# arduino_uno_with__motor_driver.net
KiCad netlist of a schematic drawn in EAGLE
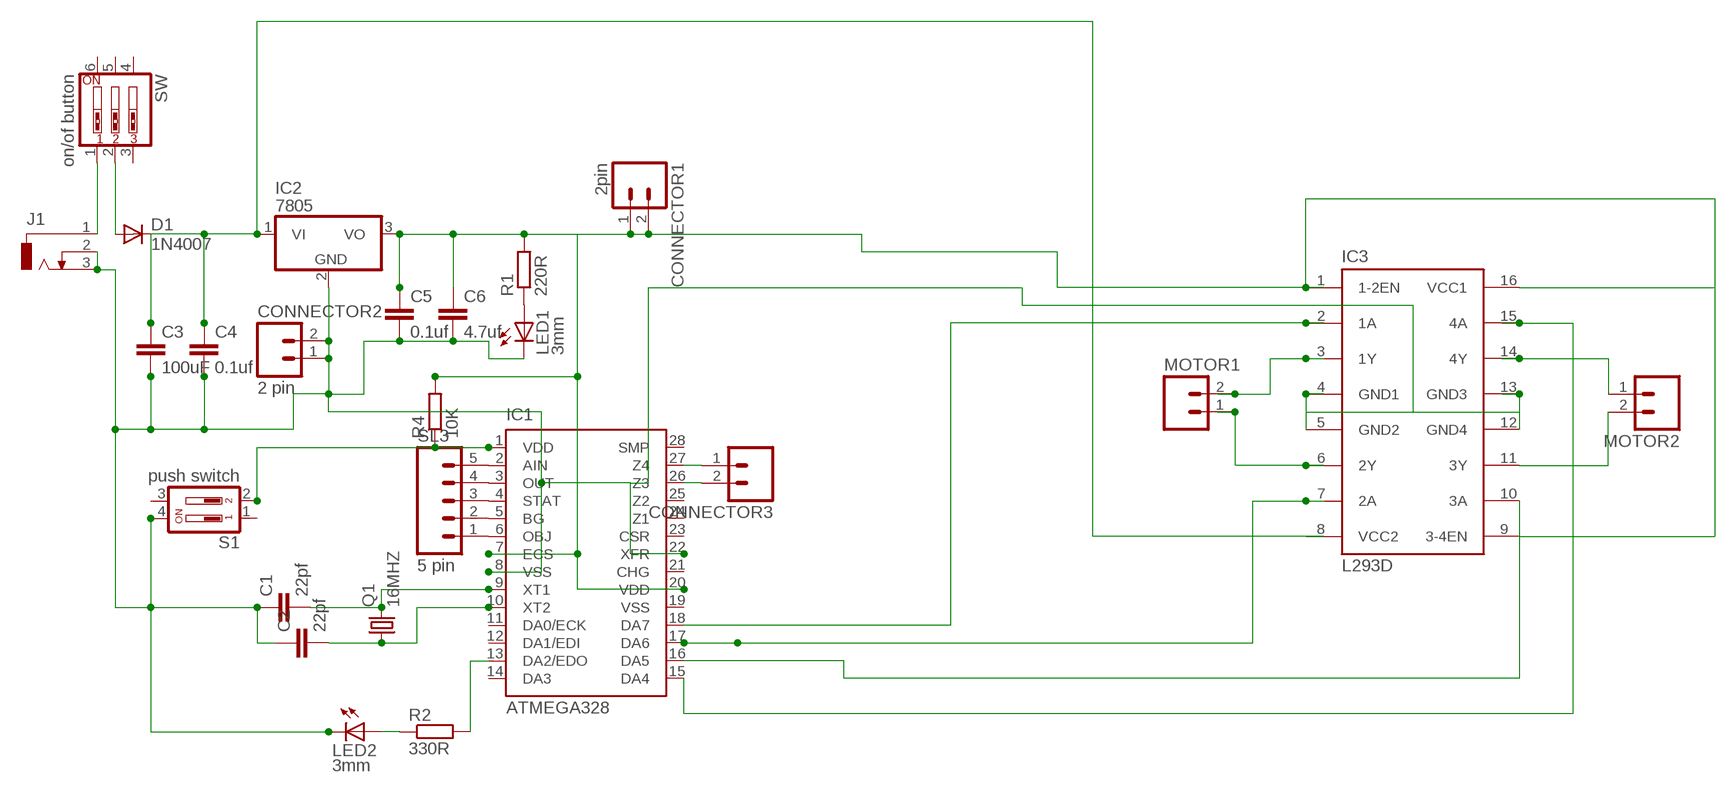
[diagram p0: schematic, sheet 1]

(export (version "E")
  (design (tool "Eeschema 10.0.6"))
  (components
    (comp (ref "C1")
      (value "22pf")
      (footprint "eagle-import:C2.5-2")
      (libsource (lib "eagle-import") (part "C2.5/2"))
    )
    (comp (ref "C2")
      (value "22pf")
      (footprint "eagle-import:C2.5-2")
      (libsource (lib "eagle-import") (part "C2.5/2"))
    )
    (comp (ref "C3")
      (value "100uF")
      (footprint "eagle-import:C2.5-2")
      (libsource (lib "eagle-import") (part "C2.5/2"))
    )
    (comp (ref "C4")
      (value "0.1uf")
      (footprint "eagle-import:C2.5-2")
      (libsource (lib "eagle-import") (part "C2.5/2"))
    )
    (comp (ref "C5")
      (value "0.1uf")
      (footprint "eagle-import:C2.5-2")
      (libsource (lib "eagle-import") (part "C2.5/2"))
    )
    (comp (ref "C6")
      (value "4.7uf")
      (footprint "eagle-import:C2.5-2")
      (libsource (lib "eagle-import") (part "C2.5/2"))
    )
    (comp (ref "CONNECTOR1")
      (value "2pin")
      (footprint "eagle-import:02P")
      (fields (field (name "OC_FARNELL") "unknown") (field (name "OC_NEWARK") "unknown"))
      (libsource (lib "eagle-import") (part "M02"))
    )
    (comp (ref "CONNECTOR2")
      (value "2 pin")
      (footprint "eagle-import:02P")
      (fields (field (name "OC_FARNELL") "unknown") (field (name "OC_NEWARK") "unknown"))
      (libsource (lib "eagle-import") (part "M02"))
    )
    (comp (ref "CONNECTOR3")
      (value "M02")
      (footprint "eagle-import:02P")
      (fields (field (name "OC_FARNELL") "unknown") (field (name "OC_NEWARK") "unknown"))
      (libsource (lib "eagle-import") (part "M02"))
    )
    (comp (ref "D1")
      (value "1N4007")
      (footprint "eagle-import:DO41-10")
      (libsource (lib "eagle-import") (part "1N4004"))
    )
    (comp (ref "IC1")
      (value "ATMEGA328")
      (footprint "eagle-import:DIL28-3")
      (libsource (lib "eagle-import") (part "QT9701BD"))
    )
    (comp (ref "IC2")
      (value "7805")
      (footprint "eagle-import:TO220V")
      (libsource (lib "eagle-import") (part "78TV6"))
    )
    (comp (ref "IC3")
      (value "L293D")
      (footprint "eagle-import:DIL16")
      (libsource (lib "eagle-import") (part "L293D"))
    )
    (comp (ref "J1")
      (value "DCJ0303")
      (footprint "eagle-import:DCJ0303")
      (libsource (lib "eagle-import") (part "DCJ0303"))
    )
    (comp (ref "LED1")
      (value "3mm")
      (footprint "eagle-import:LED3MM")
      (libsource (lib "eagle-import") (part "LED3MM"))
    )
    (comp (ref "LED2")
      (value "3mm")
      (footprint "eagle-import:LED3MM")
      (libsource (lib "eagle-import") (part "LED3MM"))
    )
    (comp (ref "MOTOR1")
      (value "M02")
      (footprint "eagle-import:02P")
      (fields (field (name "OC_FARNELL") "unknown") (field (name "OC_NEWARK") "unknown"))
      (libsource (lib "eagle-import") (part "M02"))
    )
    (comp (ref "MOTOR2")
      (value "M02")
      (footprint "eagle-import:02P")
      (libsource (lib "eagle-import") (part "M02"))
    )
    (comp (ref "Q1")
      (value "16MHZ")
      (footprint "eagle-import:HC49_S")
      (libsource (lib "eagle-import") (part "CRYSTALHC49S"))
    )
    (comp (ref "R1")
      (value "220R")
      (footprint "eagle-import:0207_10")
      (libsource (lib "eagle-import") (part "R-EU_0207/10"))
    )
    (comp (ref "R2")
      (value "330R")
      (footprint "eagle-import:0207_10")
      (libsource (lib "eagle-import") (part "R-EU_0207/10"))
    )
    (comp (ref "R4")
      (value "10K")
      (footprint "eagle-import:0207_10")
      (libsource (lib "eagle-import") (part "R-EU_0207/10"))
    )
    (comp (ref "S1")
      (value "push switch")
      (footprint "eagle-import:DP-02")
      (fields (field (name "MPN") "MCDP02"))
      (libsource (lib "eagle-import") (part "DP02"))
    )
    (comp (ref "SL3")
      (value "5 pin")
      (footprint "eagle-import:05P")
      (libsource (lib "eagle-import") (part "M05"))
    )
    (comp (ref "SW")
      (value "on/of button")
      (footprint "eagle-import:EDG-03")
      (libsource (lib "eagle-import") (part "SW_DIP-3"))
    )
  )
  (nets
    (net (code "1") (name "Net-(D1-PadA)") (class "Default")
      (node (ref "D1") (pin "A") (pinfunction "A_A") (pintype "passive"))
      (node (ref "SW") (pin "2") (pinfunction "2_2") (pintype "passive"))
    )
    (net (code "2") (name "Net-(IC1-AIN)") (class "Default")
      (node (ref "IC1") (pin "2") (pinfunction "AIN_2") (pintype "input"))
      (node (ref "SL3") (pin "5") (pinfunction "5_5") (pintype "passive"))
    )
    (net (code "3") (name "Net-(IC1-BG)") (class "Default")
      (node (ref "IC1") (pin "5") (pinfunction "BG_5") (pintype "input"))
      (node (ref "SL3") (pin "2") (pinfunction "2_2") (pintype "passive"))
    )
    (net (code "4") (name "Net-(IC1-DA2{slash}EDO)") (class "Default")
      (node (ref "IC1") (pin "13") (pinfunction "DA2/EDO_13") (pintype "output"))
      (node (ref "R2") (pin "2") (pinfunction "2_2") (pintype "passive"))
    )
    (net (code "5") (name "Net-(IC1-DA4)") (class "Default")
      (node (ref "IC1") (pin "15") (pinfunction "DA4_15") (pintype "output"))
      (node (ref "IC3") (pin "15") (pinfunction "4A_15") (pintype "input"))
    )
    (net (code "6") (name "Net-(IC1-DA5)") (class "Default")
      (node (ref "IC1") (pin "16") (pinfunction "DA5_16") (pintype "output"))
      (node (ref "IC3") (pin "10") (pinfunction "3A_10") (pintype "input"))
    )
    (net (code "7") (name "Net-(IC1-DA6)") (class "Default")
      (node (ref "IC1") (pin "17") (pinfunction "DA6_17") (pintype "output"))
      (node (ref "IC3") (pin "7") (pinfunction "2A_7") (pintype "input"))
    )
    (net (code "8") (name "Net-(IC1-DA7)") (class "Default")
      (node (ref "IC1") (pin "18") (pinfunction "DA7_18") (pintype "output"))
      (node (ref "IC3") (pin "2") (pinfunction "1A_2") (pintype "input"))
    )
    (net (code "9") (name "Net-(IC1-ECS)") (class "Default")
      (node (ref "C5") (pin "1") (pinfunction "1_1") (pintype "passive"))
      (node (ref "C6") (pin "1") (pinfunction "1_1") (pintype "passive"))
      (node (ref "CONNECTOR1") (pin "1") (pinfunction "1_1") (pintype "passive"))
      (node (ref "CONNECTOR1") (pin "2") (pinfunction "2_2") (pintype "passive"))
      (node (ref "IC1") (pin "20") (pinfunction "VDD_20") (pintype "input"))
      (node (ref "IC1") (pin "7") (pinfunction "ECS_7") (pintype "output"))
      (node (ref "IC2") (pin "3") (pinfunction "VO_3") (pintype "passive"))
      (node (ref "IC3") (pin "1") (pinfunction "1-2EN_1") (pintype "input"))
      (node (ref "IC3") (pin "16") (pinfunction "VCC1_16") (pintype "power_in"))
      (node (ref "IC3") (pin "9") (pinfunction "3-4EN_9") (pintype "input"))
      (node (ref "R1") (pin "2") (pinfunction "2_2") (pintype "passive"))
      (node (ref "R4") (pin "2") (pinfunction "2_2") (pintype "passive"))
    )
    (net (code "10") (name "Net-(IC1-OBJ)") (class "Default")
      (node (ref "IC1") (pin "6") (pinfunction "OBJ_6") (pintype "input"))
      (node (ref "SL3") (pin "1") (pinfunction "1_1") (pintype "passive"))
    )
    (net (code "11") (name "Net-(IC1-OUT)") (class "Default")
      (node (ref "IC1") (pin "3") (pinfunction "OUT_3") (pintype "output"))
      (node (ref "SL3") (pin "4") (pinfunction "4_4") (pintype "passive"))
    )
    (net (code "12") (name "Net-(IC1-STAT)") (class "Default")
      (node (ref "IC1") (pin "4") (pinfunction "STAT_4") (pintype "output"))
      (node (ref "SL3") (pin "3") (pinfunction "3_3") (pintype "passive"))
    )
    (net (code "13") (name "Net-(IC1-VDD-Pad1)") (class "Default")
      (node (ref "IC1") (pin "1") (pinfunction "VDD_1") (pintype "input"))
      (node (ref "R4") (pin "1") (pinfunction "1_1") (pintype "passive"))
      (node (ref "S1") (pin "2") (pinfunction "2_2") (pintype "passive"))
    )
    (net (code "14") (name "Net-(IC1-XFR)") (class "Default")
      (node (ref "C1") (pin "1") (pinfunction "1_1") (pintype "passive"))
      (node (ref "C2") (pin "1") (pinfunction "1_1") (pintype "passive"))
      (node (ref "C3") (pin "2") (pinfunction "2_2") (pintype "passive"))
      (node (ref "C4") (pin "2") (pinfunction "2_2") (pintype "passive"))
      (node (ref "C5") (pin "2") (pinfunction "2_2") (pintype "passive"))
      (node (ref "C6") (pin "2") (pinfunction "2_2") (pintype "passive"))
      (node (ref "CONNECTOR2") (pin "1") (pinfunction "1_1") (pintype "passive"))
      (node (ref "CONNECTOR2") (pin "2") (pinfunction "2_2") (pintype "passive"))
      (node (ref "IC1") (pin "22") (pinfunction "XFR_22") (pintype "output"))
      (node (ref "IC1") (pin "8") (pinfunction "VSS_8") (pintype "input"))
      (node (ref "IC2") (pin "2") (pinfunction "GND_2") (pintype "passive"))
      (node (ref "IC3") (pin "12") (pinfunction "GND4_12") (pintype "power_in"))
      (node (ref "IC3") (pin "13") (pinfunction "GND3_13") (pintype "power_in"))
      (node (ref "IC3") (pin "4") (pinfunction "GND1_4") (pintype "power_in"))
      (node (ref "IC3") (pin "5") (pinfunction "GND2_5") (pintype "power_in"))
      (node (ref "J1") (pin "2") (pinfunction "2_2") (pintype "passive"))
      (node (ref "J1") (pin "3") (pinfunction "3_3") (pintype "passive"))
      (node (ref "LED1") (pin "K") (pinfunction "C_K") (pintype "passive"))
      (node (ref "LED2") (pin "K") (pinfunction "C_K") (pintype "passive"))
      (node (ref "S1") (pin "4") (pinfunction "4_4") (pintype "passive"))
    )
    (net (code "15") (name "Net-(IC1-XT1)") (class "Default")
      (node (ref "C1") (pin "2") (pinfunction "2_2") (pintype "passive"))
      (node (ref "IC1") (pin "9") (pinfunction "XT1_9") (pintype "input"))
      (node (ref "Q1") (pin "2") (pinfunction "2_2") (pintype "passive"))
    )
    (net (code "16") (name "Net-(IC1-XT2)") (class "Default")
      (node (ref "C2") (pin "2") (pinfunction "2_2") (pintype "passive"))
      (node (ref "IC1") (pin "10") (pinfunction "XT2_10") (pintype "output"))
      (node (ref "Q1") (pin "1") (pinfunction "1_1") (pintype "passive"))
    )
    (net (code "17") (name "Net-(IC1-Z3)") (class "Default")
      (node (ref "CONNECTOR3") (pin "2") (pinfunction "2_2") (pintype "passive"))
      (node (ref "IC1") (pin "26") (pinfunction "Z3_26") (pintype "output"))
    )
    (net (code "18") (name "Net-(IC1-Z4)") (class "Default")
      (node (ref "CONNECTOR3") (pin "1") (pinfunction "1_1") (pintype "passive"))
      (node (ref "IC1") (pin "27") (pinfunction "Z4_27") (pintype "output"))
    )
    (net (code "19") (name "Net-(IC2-VI)") (class "Default")
      (node (ref "C3") (pin "1") (pinfunction "1_1") (pintype "passive"))
      (node (ref "C4") (pin "1") (pinfunction "1_1") (pintype "passive"))
      (node (ref "D1") (pin "C") (pinfunction "C_C") (pintype "passive"))
      (node (ref "IC2") (pin "1") (pinfunction "VI_1") (pintype "input"))
      (node (ref "IC3") (pin "8") (pinfunction "VCC2_8") (pintype "power_in"))
    )
    (net (code "20") (name "Net-(IC3-1Y)") (class "Default")
      (node (ref "IC3") (pin "3") (pinfunction "1Y_3") (pintype "output"))
      (node (ref "MOTOR1") (pin "2") (pinfunction "2_2") (pintype "passive"))
    )
    (net (code "21") (name "Net-(IC3-2Y)") (class "Default")
      (node (ref "IC3") (pin "6") (pinfunction "2Y_6") (pintype "output"))
      (node (ref "MOTOR1") (pin "1") (pinfunction "1_1") (pintype "passive"))
    )
    (net (code "22") (name "Net-(IC3-3Y)") (class "Default")
      (node (ref "IC3") (pin "11") (pinfunction "3Y_11") (pintype "output"))
      (node (ref "MOTOR2") (pin "2") (pinfunction "2_2") (pintype "passive"))
    )
    (net (code "23") (name "Net-(IC3-4Y)") (class "Default")
      (node (ref "IC3") (pin "14") (pinfunction "4Y_14") (pintype "output"))
      (node (ref "MOTOR2") (pin "1") (pinfunction "1_1") (pintype "passive"))
    )
    (net (code "24") (name "Net-(J1-Pad1)") (class "Default")
      (node (ref "J1") (pin "1") (pinfunction "1_1") (pintype "passive"))
      (node (ref "SW") (pin "1") (pinfunction "1_1") (pintype "passive"))
    )
    (net (code "25") (name "Net-(LED1-PadA)") (class "Default")
      (node (ref "LED1") (pin "A") (pinfunction "A_A") (pintype "passive"))
      (node (ref "R1") (pin "1") (pinfunction "1_1") (pintype "passive"))
    )
    (net (code "26") (name "Net-(LED2-PadA)") (class "Default")
      (node (ref "LED2") (pin "A") (pinfunction "A_A") (pintype "passive"))
      (node (ref "R2") (pin "1") (pinfunction "1_1") (pintype "passive"))
    )
    (net (code "27") (name "unconnected-(IC1-CHG-Pad21)") (class "Default")
      (node (ref "IC1") (pin "21") (pinfunction "CHG_21") (pintype "output"))
    )
    (net (code "28") (name "unconnected-(IC1-CSR-Pad23)") (class "Default")
      (node (ref "IC1") (pin "23") (pinfunction "CSR_23") (pintype "output"))
    )
    (net (code "29") (name "unconnected-(IC1-DA0{slash}ECK-Pad11)") (class "Default")
      (node (ref "IC1") (pin "11") (pinfunction "DA0/ECK_11") (pintype "output"))
    )
    (net (code "30") (name "unconnected-(IC1-DA1{slash}EDI-Pad12)") (class "Default")
      (node (ref "IC1") (pin "12") (pinfunction "DA1/EDI_12") (pintype "output"))
    )
    (net (code "31") (name "unconnected-(IC1-DA3-Pad14)") (class "Default")
      (node (ref "IC1") (pin "14") (pinfunction "DA3_14") (pintype "output"))
    )
    (net (code "32") (name "unconnected-(IC1-SMP-Pad28)") (class "Default")
      (node (ref "IC1") (pin "28") (pinfunction "SMP_28") (pintype "output"))
    )
    (net (code "33") (name "unconnected-(IC1-VSS-Pad19)") (class "Default")
      (node (ref "IC1") (pin "19") (pinfunction "VSS_19") (pintype "input"))
    )
    (net (code "34") (name "unconnected-(IC1-Z1-Pad24)") (class "Default")
      (node (ref "IC1") (pin "24") (pinfunction "Z1_24") (pintype "output"))
    )
    (net (code "35") (name "unconnected-(IC1-Z2-Pad25)") (class "Default")
      (node (ref "IC1") (pin "25") (pinfunction "Z2_25") (pintype "output"))
    )
    (net (code "36") (name "unconnected-(S1-Pad1)") (class "Default")
      (node (ref "S1") (pin "1") (pinfunction "1_1") (pintype "passive"))
    )
    (net (code "37") (name "unconnected-(S1-Pad3)") (class "Default")
      (node (ref "S1") (pin "3") (pinfunction "3_3") (pintype "passive"))
    )
    (net (code "38") (name "unconnected-(SW-Pad3)") (class "Default")
      (node (ref "SW") (pin "3") (pinfunction "3_3") (pintype "passive"))
    )
    (net (code "39") (name "unconnected-(SW-Pad4)") (class "Default")
      (node (ref "SW") (pin "4") (pinfunction "4_4") (pintype "passive"))
    )
    (net (code "40") (name "unconnected-(SW-Pad5)") (class "Default")
      (node (ref "SW") (pin "5") (pinfunction "5_5") (pintype "passive"))
    )
    (net (code "41") (name "unconnected-(SW-Pad6)") (class "Default")
      (node (ref "SW") (pin "6") (pinfunction "6_6") (pintype "passive"))
    )
  )
)
